# power_part.net
KiCad netlist of a schematic drawn in Altium Designer
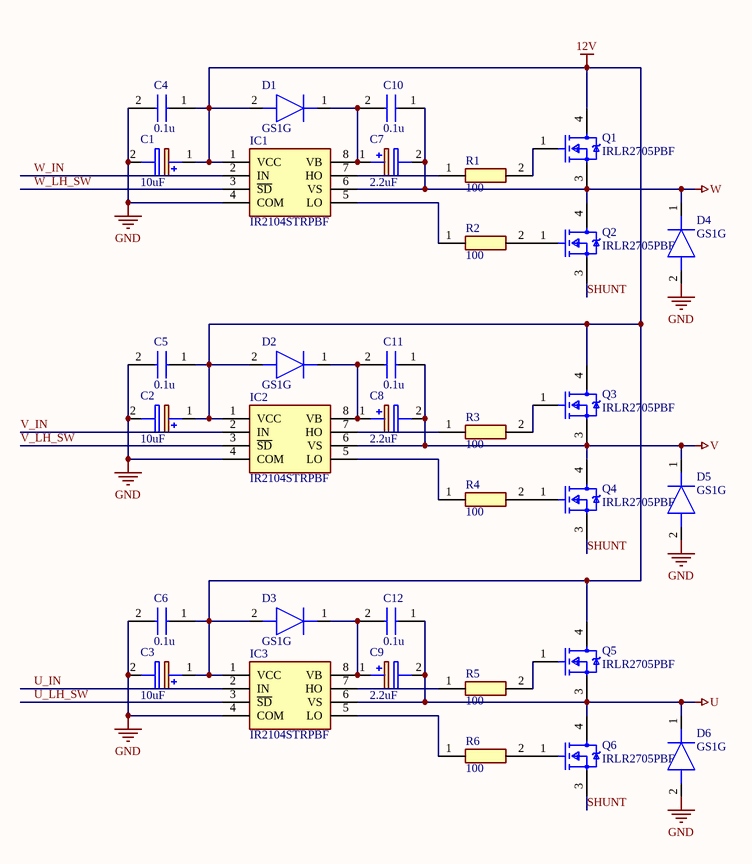
[diagram p0: power_part.SchDoc]

(export (version "E")
  (design (tool "Eeschema 10.0.6"))
  (components
    (comp (ref "C1")
      (value "10uF")
      (footprint "SamacSys:EEE1AA220WR")
      (description "Capacitor Polarised")
      (fields
        (field (name "MANUFACTURER_PART_NUMBER") "EEE-FK1E100R")
        (field (name "MOUSER PART NUMBER") "667-EEE-FK1E100R")
      )
      (libsource (lib "*") (part "EEE-FK1E100R"))
    )
    (comp (ref "C2")
      (value "10uF")
      (footprint "SamacSys:EEE1AA220WR")
      (description "Capacitor Polarised")
      (fields
        (field (name "MANUFACTURER_PART_NUMBER") "EEE-FK1E100R")
        (field (name "MOUSER PART NUMBER") "667-EEE-FK1E100R")
      )
      (libsource (lib "*") (part "EEE-FK1E100R"))
    )
    (comp (ref "C3")
      (value "10uF")
      (footprint "SamacSys:EEE1AA220WR")
      (description "Capacitor Polarised")
      (fields
        (field (name "MANUFACTURER_PART_NUMBER") "EEE-FK1E100R")
        (field (name "MOUSER PART NUMBER") "667-EEE-FK1E100R")
      )
      (libsource (lib "*") (part "EEE-FK1E100R"))
    )
    (comp (ref "C4")
      (value "0.1u")
      (footprint "SamacSys:CAPC2012X95N")
      (description "Capacitor")
      (fields
        (field (name "MANUFACTURER_PART_NUMBER") "GRM219F51H104ZA01B")
        (field (name "MOUSER PART NUMBER") "81-GRM21F51H104ZA01B")
      )
      (libsource (lib "*") (part "GRM219F51H104ZA01B"))
    )
    (comp (ref "C5")
      (value "0.1u")
      (footprint "SamacSys:CAPC2012X95N")
      (description "Capacitor")
      (fields
        (field (name "MANUFACTURER_PART_NUMBER") "GRM219F51H104ZA01B")
        (field (name "MOUSER PART NUMBER") "81-GRM21F51H104ZA01B")
      )
      (libsource (lib "*") (part "GRM219F51H104ZA01B"))
    )
    (comp (ref "C6")
      (value "0.1u")
      (footprint "SamacSys:CAPC2012X95N")
      (description "Capacitor")
      (fields
        (field (name "MANUFACTURER_PART_NUMBER") "GRM219F51H104ZA01B")
        (field (name "MOUSER PART NUMBER") "81-GRM21F51H104ZA01B")
      )
      (libsource (lib "*") (part "GRM219F51H104ZA01B"))
    )
    (comp (ref "C7")
      (value "2.2uF")
      (footprint "SamacSys:EEE1AA220WR")
      (description "Capacitor Polarised")
      (fields
        (field (name "MANUFACTURER_PART_NUMBER") "EEE-HB1H2R2AR")
        (field (name "MOUSER PART NUMBER") "667-EEE-HB1H2R2AR")
      )
      (libsource (lib "*") (part "EEE-HB1H2R2AR"))
    )
    (comp (ref "C8")
      (value "2.2uF")
      (footprint "SamacSys:EEE1AA220WR")
      (description "Capacitor Polarised")
      (fields
        (field (name "MANUFACTURER_PART_NUMBER") "EEE-HB1H2R2AR")
        (field (name "MOUSER PART NUMBER") "667-EEE-HB1H2R2AR")
      )
      (libsource (lib "*") (part "EEE-HB1H2R2AR"))
    )
    (comp (ref "C9")
      (value "2.2uF")
      (footprint "SamacSys:EEE1AA220WR")
      (description "Capacitor Polarised")
      (fields
        (field (name "MANUFACTURER_PART_NUMBER") "EEE-HB1H2R2AR")
        (field (name "MOUSER PART NUMBER") "667-EEE-HB1H2R2AR")
      )
      (libsource (lib "*") (part "EEE-HB1H2R2AR"))
    )
    (comp (ref "C10")
      (value "0.1u")
      (footprint "SamacSys:CAPC2012X95N")
      (description "Capacitor")
      (fields
        (field (name "MANUFACTURER_PART_NUMBER") "GRM219F51H104ZA01B")
        (field (name "MOUSER PART NUMBER") "81-GRM21F51H104ZA01B")
      )
      (libsource (lib "*") (part "GRM219F51H104ZA01B"))
    )
    (comp (ref "C11")
      (value "0.1u")
      (footprint "SamacSys:CAPC2012X95N")
      (description "Capacitor")
      (fields
        (field (name "MANUFACTURER_PART_NUMBER") "GRM219F51H104ZA01B")
        (field (name "MOUSER PART NUMBER") "81-GRM21F51H104ZA01B")
      )
      (libsource (lib "*") (part "GRM219F51H104ZA01B"))
    )
    (comp (ref "C12")
      (value "0.1u")
      (footprint "SamacSys:CAPC2012X95N")
      (description "Capacitor")
      (fields
        (field (name "MANUFACTURER_PART_NUMBER") "GRM219F51H104ZA01B")
        (field (name "MOUSER PART NUMBER") "81-GRM21F51H104ZA01B")
      )
      (libsource (lib "*") (part "GRM219F51H104ZA01B"))
    )
    (comp (ref "D1")
      (value "GS1G")
      (footprint "SamacSys:DIOM5027X244N")
      (description "Diode")
      (libsource (lib "*") (part "GS1G"))
    )
    (comp (ref "D2")
      (value "GS1G")
      (footprint "SamacSys:DIOM5027X244N")
      (description "Diode")
      (libsource (lib "*") (part "GS1G"))
    )
    (comp (ref "D3")
      (value "GS1G")
      (footprint "SamacSys:DIOM5027X244N")
      (description "Diode")
      (libsource (lib "*") (part "GS1G"))
    )
    (comp (ref "D4")
      (value "GS1G")
      (footprint "SamacSys:DIOM5027X244N")
      (description "Diode")
      (libsource (lib "*") (part "GS1G"))
    )
    (comp (ref "D5")
      (value "GS1G")
      (footprint "SamacSys:DIOM5027X244N")
      (description "Diode")
      (libsource (lib "*") (part "GS1G"))
    )
    (comp (ref "D6")
      (value "GS1G")
      (footprint "SamacSys:DIOM5027X244N")
      (description "Diode")
      (libsource (lib "*") (part "GS1G"))
    )
    (comp (ref "IC1")
      (value "IR2104STRPBF")
      (footprint "SamacSys:SOIC127P600X175-8N")
      (description "Integrated Circuit")
      (fields (field (name "MOUSER PART NUMBER") "942-IR2104STRPBF"))
      (libsource (lib "*") (part "IR2104STRPBF"))
    )
    (comp (ref "IC2")
      (value "IR2104STRPBF")
      (footprint "SamacSys:SOIC127P600X175-8N")
      (description "Integrated Circuit")
      (fields (field (name "MOUSER PART NUMBER") "942-IR2104STRPBF"))
      (libsource (lib "*") (part "IR2104STRPBF"))
    )
    (comp (ref "IC3")
      (value "IR2104STRPBF")
      (footprint "SamacSys:SOIC127P600X175-8N")
      (description "Integrated Circuit")
      (fields (field (name "MOUSER PART NUMBER") "942-IR2104STRPBF"))
      (libsource (lib "*") (part "IR2104STRPBF"))
    )
    (comp (ref "Q1")
      (value "IRLR2705PBF")
      (footprint "FP-PG-TO252-3-MFG")
      (description "MOSFET N-CH 55V 44A DPAK")
      (fields
        (field (name "OCTOPART") "https://octopart.com/irfr1205trpbf-infineon-65874068")
        (field (name "MANUFACTURER") "Infineon")
      )
      (libsource (lib "Altium Content Vault") (part "cdf1c68f84cb049e5ebc85739c3fcf6"))
    )
    (comp (ref "Q2")
      (value "IRLR2705PBF")
      (footprint "FP-PG-TO252-3-MFG")
      (description "MOSFET N-CH 55V 44A DPAK")
      (fields
        (field (name "OCTOPART") "https://octopart.com/irfr1205trpbf-infineon-65874068")
        (field (name "MANUFACTURER") "Infineon")
      )
      (libsource (lib "Altium Content Vault") (part "cdf1c68f84cb049e5ebc85739c3fcf6"))
    )
    (comp (ref "Q3")
      (value "IRLR2705PBF")
      (footprint "FP-PG-TO252-3-MFG")
      (description "MOSFET N-CH 55V 44A DPAK")
      (fields
        (field (name "OCTOPART") "https://octopart.com/irfr1205trpbf-infineon-65874068")
        (field (name "MANUFACTURER") "Infineon")
      )
      (libsource (lib "Altium Content Vault") (part "cdf1c68f84cb049e5ebc85739c3fcf6"))
    )
    (comp (ref "Q4")
      (value "IRLR2705PBF")
      (footprint "FP-PG-TO252-3-MFG")
      (description "MOSFET N-CH 55V 44A DPAK")
      (fields
        (field (name "OCTOPART") "https://octopart.com/irfr1205trpbf-infineon-65874068")
        (field (name "MANUFACTURER") "Infineon")
      )
      (libsource (lib "Altium Content Vault") (part "cdf1c68f84cb049e5ebc85739c3fcf6"))
    )
    (comp (ref "Q5")
      (value "IRLR2705PBF")
      (footprint "FP-PG-TO252-3-MFG")
      (description "MOSFET N-CH 55V 44A DPAK")
      (fields
        (field (name "OCTOPART") "https://octopart.com/irfr1205trpbf-infineon-65874068")
        (field (name "MANUFACTURER") "Infineon")
      )
      (libsource (lib "Altium Content Vault") (part "cdf1c68f84cb049e5ebc85739c3fcf6"))
    )
    (comp (ref "Q6")
      (value "IRLR2705PBF")
      (footprint "FP-PG-TO252-3-MFG")
      (description "MOSFET N-CH 55V 44A DPAK")
      (fields
        (field (name "OCTOPART") "https://octopart.com/irfr1205trpbf-infineon-65874068")
        (field (name "MANUFACTURER") "Infineon")
      )
      (libsource (lib "Altium Content Vault") (part "cdf1c68f84cb049e5ebc85739c3fcf6"))
    )
    (comp (ref "R1")
      (value "100")
      (footprint "SamacSys:RESC2012X60N")
      (description "Resistor")
      (fields
        (field (name "MANUFACTURER_PART_NUMBER") "RC0805JR-0720RL")
        (field (name "MOUSER PART NUMBER") "603-RC0805JR-0720RL")
      )
      (libsource (lib "*") (part "RC0805JR-0720RL"))
    )
    (comp (ref "R2")
      (value "100")
      (footprint "SamacSys:RESC2012X60N")
      (description "Resistor")
      (fields
        (field (name "MANUFACTURER_PART_NUMBER") "RC0805JR-0720RL")
        (field (name "MOUSER PART NUMBER") "603-RC0805JR-0720RL")
      )
      (libsource (lib "*") (part "RC0805JR-0720RL"))
    )
    (comp (ref "R3")
      (value "100")
      (footprint "SamacSys:RESC2012X60N")
      (description "Resistor")
      (fields
        (field (name "MANUFACTURER_PART_NUMBER") "RC0805JR-0720RL")
        (field (name "MOUSER PART NUMBER") "603-RC0805JR-0720RL")
      )
      (libsource (lib "*") (part "RC0805JR-0720RL"))
    )
    (comp (ref "R4")
      (value "100")
      (footprint "SamacSys:RESC2012X60N")
      (description "Resistor")
      (fields
        (field (name "MANUFACTURER_PART_NUMBER") "RC0805JR-0720RL")
        (field (name "MOUSER PART NUMBER") "603-RC0805JR-0720RL")
      )
      (libsource (lib "*") (part "RC0805JR-0720RL"))
    )
    (comp (ref "R5")
      (value "100")
      (footprint "SamacSys:RESC2012X60N")
      (description "Resistor")
      (fields
        (field (name "MANUFACTURER_PART_NUMBER") "RC0805JR-0720RL")
        (field (name "MOUSER PART NUMBER") "603-RC0805JR-0720RL")
      )
      (libsource (lib "*") (part "RC0805JR-0720RL"))
    )
    (comp (ref "R6")
      (value "100")
      (footprint "SamacSys:RESC2012X60N")
      (description "Resistor")
      (fields
        (field (name "MANUFACTURER_PART_NUMBER") "RC0805JR-0720RL")
        (field (name "MOUSER PART NUMBER") "603-RC0805JR-0720RL")
      )
      (libsource (lib "*") (part "RC0805JR-0720RL"))
    )
  )
  (nets
    (net (code "1") (name "/SHUNT") (class "Default")
      (node (ref "Q2") (pin "3") (pinfunction "S_3") (pintype "passive"))
      (node (ref "Q4") (pin "3") (pinfunction "S_3") (pintype "passive"))
      (node (ref "Q6") (pin "3") (pinfunction "S_3") (pintype "passive"))
    )
    (net (code "2") (name "/U_IN") (class "Default")
      (node (ref "IC3") (pin "2") (pinfunction "IN_2") (pintype "passive"))
    )
    (net (code "3") (name "/U_LH_SW") (class "Default")
      (node (ref "IC3") (pin "3") (pinfunction "~{SD}_3") (pintype "passive"))
    )
    (net (code "4") (name "/V_IN") (class "Default")
      (node (ref "IC2") (pin "2") (pinfunction "IN_2") (pintype "passive"))
    )
    (net (code "5") (name "/V_LH_SW") (class "Default")
      (node (ref "IC2") (pin "3") (pinfunction "~{SD}_3") (pintype "passive"))
    )
    (net (code "6") (name "/W_IN") (class "Default")
      (node (ref "IC1") (pin "2") (pinfunction "IN_2") (pintype "passive"))
    )
    (net (code "7") (name "/W_LH_SW") (class "Default")
      (node (ref "IC1") (pin "3") (pinfunction "~{SD}_3") (pintype "passive"))
    )
    (net (code "8") (name "12V") (class "Default")
      (node (ref "C1") (pin "1") (pinfunction "+_1") (pintype "passive"))
      (node (ref "C2") (pin "1") (pinfunction "+_1") (pintype "passive"))
      (node (ref "C3") (pin "1") (pinfunction "+_1") (pintype "passive"))
      (node (ref "C4") (pin "1") (pinfunction "1_1") (pintype "passive"))
      (node (ref "C5") (pin "1") (pinfunction "1_1") (pintype "passive"))
      (node (ref "C6") (pin "1") (pinfunction "1_1") (pintype "passive"))
      (node (ref "D1") (pin "2") (pinfunction "A_2") (pintype "passive"))
      (node (ref "D2") (pin "2") (pinfunction "A_2") (pintype "passive"))
      (node (ref "D3") (pin "2") (pinfunction "A_2") (pintype "passive"))
      (node (ref "IC1") (pin "1") (pinfunction "VCC_1") (pintype "passive"))
      (node (ref "IC2") (pin "1") (pinfunction "VCC_1") (pintype "passive"))
      (node (ref "IC3") (pin "1") (pinfunction "VCC_1") (pintype "passive"))
      (node (ref "Q1") (pin "4") (pinfunction "D_4") (pintype "passive"))
      (node (ref "Q3") (pin "4") (pinfunction "D_4") (pintype "passive"))
      (node (ref "Q5") (pin "4") (pinfunction "D_4") (pintype "passive"))
    )
    (net (code "9") (name "GND") (class "Default")
      (node (ref "C1") (pin "2") (pinfunction "-_2") (pintype "passive"))
      (node (ref "C2") (pin "2") (pinfunction "-_2") (pintype "passive"))
      (node (ref "C3") (pin "2") (pinfunction "-_2") (pintype "passive"))
      (node (ref "C4") (pin "2") (pinfunction "2_2") (pintype "passive"))
      (node (ref "C5") (pin "2") (pinfunction "2_2") (pintype "passive"))
      (node (ref "C6") (pin "2") (pinfunction "2_2") (pintype "passive"))
      (node (ref "D4") (pin "2") (pinfunction "A_2") (pintype "passive"))
      (node (ref "D5") (pin "2") (pinfunction "A_2") (pintype "passive"))
      (node (ref "D6") (pin "2") (pinfunction "A_2") (pintype "passive"))
      (node (ref "IC1") (pin "4") (pinfunction "COM_4") (pintype "passive"))
      (node (ref "IC2") (pin "4") (pinfunction "COM_4") (pintype "passive"))
      (node (ref "IC3") (pin "4") (pinfunction "COM_4") (pintype "passive"))
    )
    (net (code "10") (name "Net-(C7-+)") (class "Default")
      (node (ref "C10") (pin "2") (pinfunction "2_2") (pintype "passive"))
      (node (ref "C7") (pin "1") (pinfunction "+_1") (pintype "passive"))
      (node (ref "D1") (pin "1") (pinfunction "K_1") (pintype "passive"))
      (node (ref "IC1") (pin "8") (pinfunction "VB_8") (pintype "passive"))
    )
    (net (code "11") (name "Net-(C8-+)") (class "Default")
      (node (ref "C11") (pin "2") (pinfunction "2_2") (pintype "passive"))
      (node (ref "C8") (pin "1") (pinfunction "+_1") (pintype "passive"))
      (node (ref "D2") (pin "1") (pinfunction "K_1") (pintype "passive"))
      (node (ref "IC2") (pin "8") (pinfunction "VB_8") (pintype "passive"))
    )
    (net (code "12") (name "Net-(C9-+)") (class "Default")
      (node (ref "C12") (pin "2") (pinfunction "2_2") (pintype "passive"))
      (node (ref "C9") (pin "1") (pinfunction "+_1") (pintype "passive"))
      (node (ref "D3") (pin "1") (pinfunction "K_1") (pintype "passive"))
      (node (ref "IC3") (pin "8") (pinfunction "VB_8") (pintype "passive"))
    )
    (net (code "13") (name "Net-(IC1-HO)") (class "Default")
      (node (ref "IC1") (pin "7") (pinfunction "HO_7") (pintype "passive"))
      (node (ref "R1") (pin "1") (pinfunction "1_1") (pintype "passive"))
    )
    (net (code "14") (name "Net-(IC1-LO)") (class "Default")
      (node (ref "IC1") (pin "5") (pinfunction "LO_5") (pintype "passive"))
      (node (ref "R2") (pin "1") (pinfunction "1_1") (pintype "passive"))
    )
    (net (code "15") (name "Net-(IC2-HO)") (class "Default")
      (node (ref "IC2") (pin "7") (pinfunction "HO_7") (pintype "passive"))
      (node (ref "R3") (pin "1") (pinfunction "1_1") (pintype "passive"))
    )
    (net (code "16") (name "Net-(IC2-LO)") (class "Default")
      (node (ref "IC2") (pin "5") (pinfunction "LO_5") (pintype "passive"))
      (node (ref "R4") (pin "1") (pinfunction "1_1") (pintype "passive"))
    )
    (net (code "17") (name "Net-(IC3-HO)") (class "Default")
      (node (ref "IC3") (pin "7") (pinfunction "HO_7") (pintype "passive"))
      (node (ref "R5") (pin "1") (pinfunction "1_1") (pintype "passive"))
    )
    (net (code "18") (name "Net-(IC3-LO)") (class "Default")
      (node (ref "IC3") (pin "5") (pinfunction "LO_5") (pintype "passive"))
      (node (ref "R6") (pin "1") (pinfunction "1_1") (pintype "passive"))
    )
    (net (code "19") (name "Net-(Q1-G)") (class "Default")
      (node (ref "Q1") (pin "1") (pinfunction "G_1") (pintype "passive"))
      (node (ref "R1") (pin "2") (pinfunction "2_2") (pintype "passive"))
    )
    (net (code "20") (name "Net-(Q2-G)") (class "Default")
      (node (ref "Q2") (pin "1") (pinfunction "G_1") (pintype "passive"))
      (node (ref "R2") (pin "2") (pinfunction "2_2") (pintype "passive"))
    )
    (net (code "21") (name "Net-(Q3-G)") (class "Default")
      (node (ref "Q3") (pin "1") (pinfunction "G_1") (pintype "passive"))
      (node (ref "R3") (pin "2") (pinfunction "2_2") (pintype "passive"))
    )
    (net (code "22") (name "Net-(Q4-G)") (class "Default")
      (node (ref "Q4") (pin "1") (pinfunction "G_1") (pintype "passive"))
      (node (ref "R4") (pin "2") (pinfunction "2_2") (pintype "passive"))
    )
    (net (code "23") (name "Net-(Q5-G)") (class "Default")
      (node (ref "Q5") (pin "1") (pinfunction "G_1") (pintype "passive"))
      (node (ref "R5") (pin "2") (pinfunction "2_2") (pintype "passive"))
    )
    (net (code "24") (name "Net-(Q6-G)") (class "Default")
      (node (ref "Q6") (pin "1") (pinfunction "G_1") (pintype "passive"))
      (node (ref "R6") (pin "2") (pinfunction "2_2") (pintype "passive"))
    )
    (net (code "25") (name "U") (class "Default")
      (node (ref "C12") (pin "1") (pinfunction "1_1") (pintype "passive"))
      (node (ref "C9") (pin "2") (pinfunction "-_2") (pintype "passive"))
      (node (ref "D6") (pin "1") (pinfunction "K_1") (pintype "passive"))
      (node (ref "IC3") (pin "6") (pinfunction "VS_6") (pintype "passive"))
      (node (ref "Q5") (pin "3") (pinfunction "S_3") (pintype "passive"))
      (node (ref "Q6") (pin "4") (pinfunction "D_4") (pintype "passive"))
    )
    (net (code "26") (name "V") (class "Default")
      (node (ref "C11") (pin "1") (pinfunction "1_1") (pintype "passive"))
      (node (ref "C8") (pin "2") (pinfunction "-_2") (pintype "passive"))
      (node (ref "D5") (pin "1") (pinfunction "K_1") (pintype "passive"))
      (node (ref "IC2") (pin "6") (pinfunction "VS_6") (pintype "passive"))
      (node (ref "Q3") (pin "3") (pinfunction "S_3") (pintype "passive"))
      (node (ref "Q4") (pin "4") (pinfunction "D_4") (pintype "passive"))
    )
    (net (code "27") (name "W") (class "Default")
      (node (ref "C10") (pin "1") (pinfunction "1_1") (pintype "passive"))
      (node (ref "C7") (pin "2") (pinfunction "-_2") (pintype "passive"))
      (node (ref "D4") (pin "1") (pinfunction "K_1") (pintype "passive"))
      (node (ref "IC1") (pin "6") (pinfunction "VS_6") (pintype "passive"))
      (node (ref "Q1") (pin "3") (pinfunction "S_3") (pintype "passive"))
      (node (ref "Q2") (pin "4") (pinfunction "D_4") (pintype "passive"))
    )
  )
)
